# apple_all_pt3.net
KiCad netlist of a schematic drawn in EAGLE
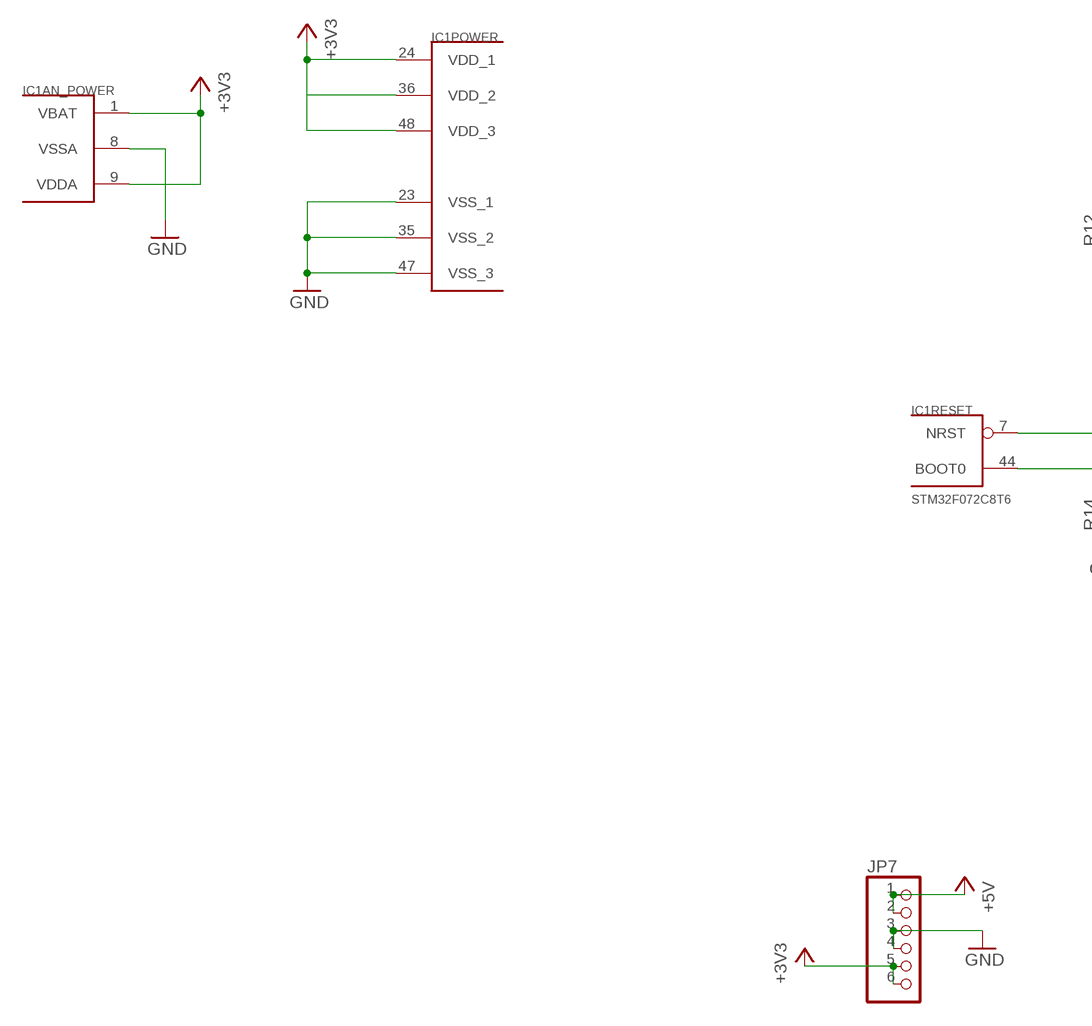
[diagram p0: schematic, sheet 1, part 1 of 2]
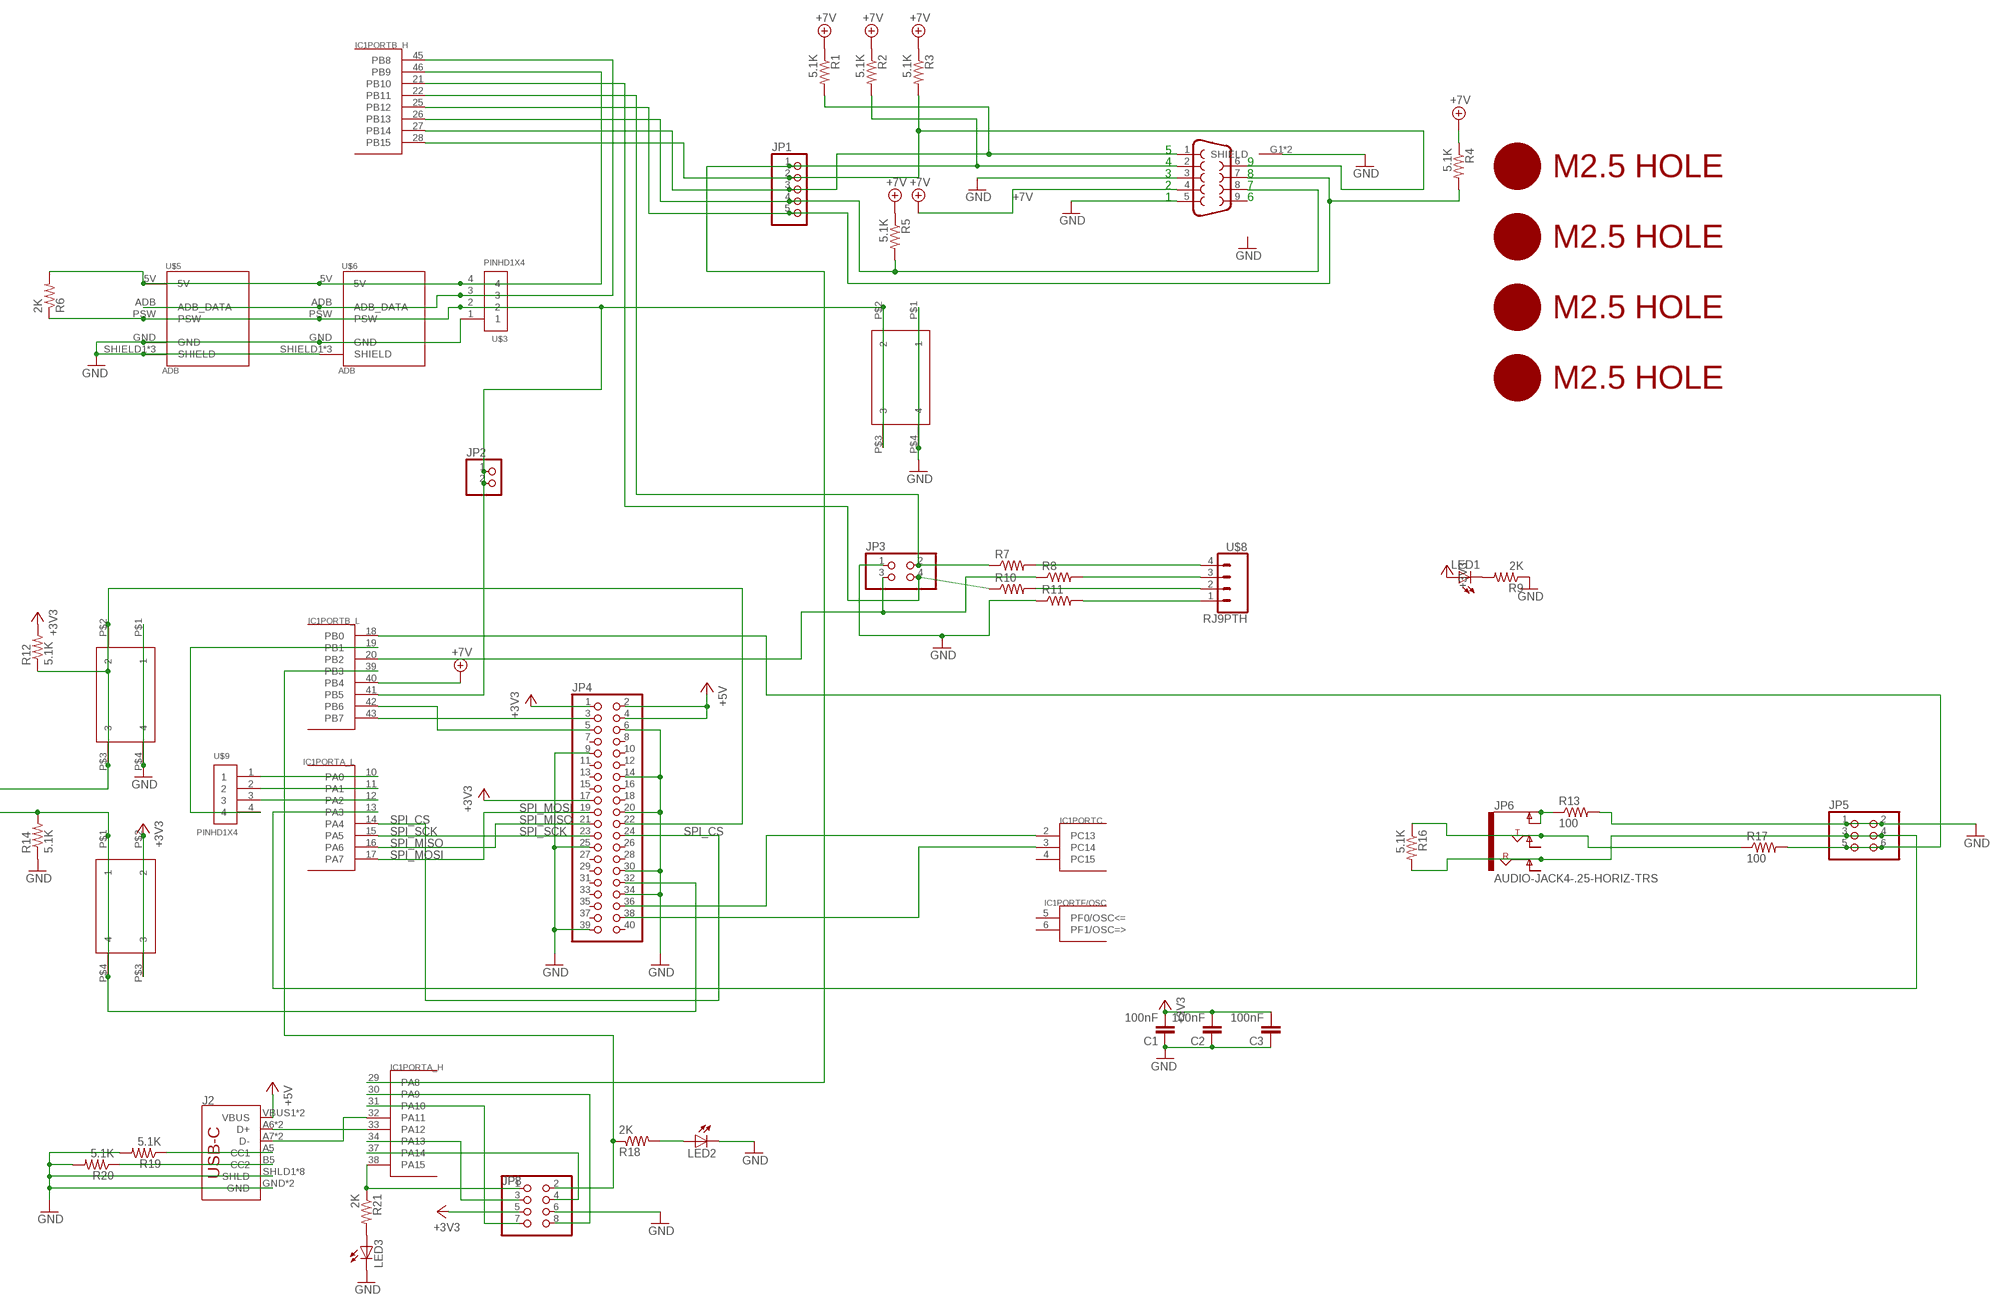
[diagram p1: schematic, sheet 1, part 2 of 2]

(export (version "E")
  (design (tool "Eeschema 10.0.6"))
  (components
    (comp (ref "C1")
      (value "100nF")
      (footprint "eagle-import:0805@1")
      (libsource (lib "eagle-import") (part "CAP0805"))
    )
    (comp (ref "C2")
      (value "100nF")
      (footprint "eagle-import:0805@1")
      (libsource (lib "eagle-import") (part "CAP0805"))
    )
    (comp (ref "C3")
      (value "100nF")
      (footprint "eagle-import:0805@1")
      (libsource (lib "eagle-import") (part "CAP0805"))
    )
    (comp (ref "IC1")
      (value "STM32F072C8T6")
      (footprint "eagle-import:TQFP48")
      (libsource (lib "eagle-import") (part "STM32F072C8T6"))
    )
    (comp (ref "J1")
      (value "DB9FEMALE")
      (footprint "eagle-import:DB9")
      (libsource (lib "eagle-import") (part "DB9FEMALE"))
    )
    (comp (ref "J2")
      (value "USB_C16PIN")
      (footprint "eagle-import:USB-C-16P")
      (libsource (lib "eagle-import") (part "USB_C16PIN"))
    )
    (comp (ref "JP1")
      (value "PINHD-1X5")
      (footprint "eagle-import:1X05")
      (libsource (lib "eagle-import") (part "PINHD-1X5"))
    )
    (comp (ref "JP2")
      (value "PINHD-1X2")
      (footprint "eagle-import:1X02")
      (libsource (lib "eagle-import") (part "PINHD-1X2"))
    )
    (comp (ref "JP3")
      (value "PINHD-2X2")
      (footprint "eagle-import:2X02")
      (libsource (lib "eagle-import") (part "PINHD-2X2"))
    )
    (comp (ref "JP4")
      (value "PINHD-2X20-BIG")
      (footprint "eagle-import:2X20-BIG")
      (libsource (lib "eagle-import") (part "PINHD-2X20-BIG"))
    )
    (comp (ref "JP5")
      (value "PINHD-2X3")
      (footprint "eagle-import:2X03")
      (libsource (lib "eagle-import") (part "PINHD-2X3"))
    )
    (comp (ref "JP6")
      (value "AUDIO-JACK4-.25-HORIZ-TRS")
      (footprint "eagle-import:AUDIO-JACK-.25-INCH-HORIZ-PTH")
      (libsource (lib "eagle-import") (part "AUDIO-JACK4-.25-HORIZ-TRS"))
    )
    (comp (ref "JP7")
      (value "PINHD-1X6CB")
      (footprint "eagle-import:1X06-CLEANBIG")
      (libsource (lib "eagle-import") (part "PINHD-1X6CB"))
    )
    (comp (ref "JP8")
      (value "PINHD-2X4")
      (footprint "eagle-import:2X04")
      (libsource (lib "eagle-import") (part "PINHD-2X4"))
    )
    (comp (ref "LED1")
      (value "LEDCHIP-LED0805")
      (footprint "eagle-import:CHIP-LED0805")
      (libsource (lib "eagle-import") (part "LEDCHIP-LED0805"))
    )
    (comp (ref "LED2")
      (value "LEDCHIP-LED0805")
      (footprint "eagle-import:CHIP-LED0805")
      (libsource (lib "eagle-import") (part "LEDCHIP-LED0805"))
    )
    (comp (ref "LED3")
      (value "LEDCHIP-LED0805")
      (footprint "eagle-import:CHIP-LED0805")
      (libsource (lib "eagle-import") (part "LEDCHIP-LED0805"))
    )
    (comp (ref "R1")
      (value "5.1K")
      (footprint "eagle-import:0805")
      (libsource (lib "eagle-import") (part "RESISTOR0805-RES"))
    )
    (comp (ref "R2")
      (value "5.1K")
      (footprint "eagle-import:0805")
      (libsource (lib "eagle-import") (part "RESISTOR0805-RES"))
    )
    (comp (ref "R3")
      (value "5.1K")
      (footprint "eagle-import:0805")
      (libsource (lib "eagle-import") (part "RESISTOR0805-RES"))
    )
    (comp (ref "R4")
      (value "5.1K")
      (footprint "eagle-import:0805")
      (libsource (lib "eagle-import") (part "RESISTOR0805-RES"))
    )
    (comp (ref "R5")
      (value "5.1K")
      (footprint "eagle-import:0805")
      (libsource (lib "eagle-import") (part "RESISTOR0805-RES"))
    )
    (comp (ref "R6")
      (value "2K")
      (footprint "eagle-import:0805")
      (libsource (lib "eagle-import") (part "RESISTOR0805-RES"))
    )
    (comp (ref "R7")
      (value "200")
      (footprint "eagle-import:0805")
      (libsource (lib "eagle-import") (part "RESISTOR0805-RES"))
    )
    (comp (ref "R8")
      (value "200")
      (footprint "eagle-import:0805")
      (libsource (lib "eagle-import") (part "RESISTOR0805-RES"))
    )
    (comp (ref "R9")
      (value "2K")
      (footprint "eagle-import:0805")
      (libsource (lib "eagle-import") (part "RESISTOR0805-RES"))
    )
    (comp (ref "R10")
      (value "200")
      (footprint "eagle-import:0805")
      (libsource (lib "eagle-import") (part "RESISTOR0805-RES"))
    )
    (comp (ref "R11")
      (value "200")
      (footprint "eagle-import:0805")
      (libsource (lib "eagle-import") (part "RESISTOR0805-RES"))
    )
    (comp (ref "R12")
      (value "5.1K")
      (footprint "eagle-import:0805")
      (libsource (lib "eagle-import") (part "RESISTOR0805-RES"))
    )
    (comp (ref "R13")
      (value "100")
      (footprint "eagle-import:0805")
      (libsource (lib "eagle-import") (part "RESISTOR0805-RES"))
    )
    (comp (ref "R14")
      (value "5.1K")
      (footprint "eagle-import:0805")
      (libsource (lib "eagle-import") (part "RESISTOR0805-RES"))
    )
    (comp (ref "R16")
      (value "5.1K")
      (footprint "eagle-import:0805")
      (libsource (lib "eagle-import") (part "RESISTOR0805-RES"))
    )
    (comp (ref "R17")
      (value "100")
      (footprint "eagle-import:0805")
      (libsource (lib "eagle-import") (part "RESISTOR0805-RES"))
    )
    (comp (ref "R18")
      (value "2K")
      (footprint "eagle-import:0805")
      (libsource (lib "eagle-import") (part "RESISTOR0805-RES"))
    )
    (comp (ref "R19")
      (value "5.1K")
      (footprint "eagle-import:0805")
      (libsource (lib "eagle-import") (part "RESISTOR0805-RES"))
    )
    (comp (ref "R20")
      (value "5.1K")
      (footprint "eagle-import:0805")
      (libsource (lib "eagle-import") (part "RESISTOR0805-RES"))
    )
    (comp (ref "R21")
      (value "2K")
      (footprint "eagle-import:0805")
      (libsource (lib "eagle-import") (part "RESISTOR0805-RES"))
    )
    (comp (ref "SW1")
      (value "324_SW")
      (footprint "eagle-import:342_SWICH_FOOT")
      (libsource (lib "eagle-import") (part "324_SW"))
    )
    (comp (ref "SW2")
      (value "324_SW")
      (footprint "eagle-import:342_SWICH_FOOT")
      (libsource (lib "eagle-import") (part "324_SW"))
    )
    (comp (ref "SW3")
      (value "324_SW")
      (footprint "eagle-import:342_SWICH_FOOT")
      (libsource (lib "eagle-import") (part "324_SW"))
    )
    (comp (ref "U$1")
      (value "M2.5HOLE")
      (footprint "eagle-import:M2.5HOLE")
      (libsource (lib "eagle-import") (part "M2.5HOLE"))
    )
    (comp (ref "U$2")
      (value "M2.5HOLE")
      (footprint "eagle-import:M2.5HOLE")
      (libsource (lib "eagle-import") (part "M2.5HOLE"))
    )
    (comp (ref "U$3")
      (value "PINHD1X4")
      (footprint "eagle-import:1X04-CLEANBIG")
      (libsource (lib "eagle-import") (part "PINHD1X4"))
    )
    (comp (ref "U$4")
      (value "M2.5HOLE")
      (footprint "eagle-import:M2.5HOLE")
      (libsource (lib "eagle-import") (part "M2.5HOLE"))
    )
    (comp (ref "U$5")
      (value "ADB")
      (footprint "eagle-import:DIN4")
      (libsource (lib "eagle-import") (part "ADB"))
    )
    (comp (ref "U$6")
      (value "ADB")
      (footprint "eagle-import:DIN4")
      (libsource (lib "eagle-import") (part "ADB"))
    )
    (comp (ref "U$7")
      (value "M2.5HOLE")
      (footprint "eagle-import:M2.5HOLE")
      (libsource (lib "eagle-import") (part "M2.5HOLE"))
    )
    (comp (ref "U$8")
      (value "RJ9PTH")
      (footprint "eagle-import:RJ9")
      (libsource (lib "eagle-import") (part "RJ9PTH"))
    )
    (comp (ref "U$9")
      (value "PINHD1X4")
      (footprint "eagle-import:1X04-CLEANBIG")
      (libsource (lib "eagle-import") (part "PINHD1X4"))
    )
  )
  (nets
    (net (code "1") (name "+3V3") (class "Default")
      (node (ref "C1") (pin "2") (pinfunction "2_2") (pintype "passive"))
      (node (ref "C2") (pin "2") (pinfunction "2_2") (pintype "passive"))
      (node (ref "C3") (pin "2") (pinfunction "2_2") (pintype "passive"))
      (node (ref "IC1") (pin "1") (pinfunction "VBAT_1") (pintype "power_in"))
      (node (ref "IC1") (pin "24") (pinfunction "VDD_1_24") (pintype "power_in"))
      (node (ref "IC1") (pin "36") (pinfunction "VDD_2_36") (pintype "power_in"))
      (node (ref "IC1") (pin "48") (pinfunction "VDD_3_48") (pintype "power_in"))
      (node (ref "IC1") (pin "9") (pinfunction "VDDA_9") (pintype "power_in"))
      (node (ref "JP4") (pin "1") (pinfunction "1_1") (pintype "passive"))
      (node (ref "JP4") (pin "17") (pinfunction "17_17") (pintype "passive"))
      (node (ref "JP7") (pin "5") (pinfunction "5_5") (pintype "passive"))
      (node (ref "JP7") (pin "6") (pinfunction "6_6") (pintype "passive"))
      (node (ref "JP8") (pin "5") (pinfunction "5_5") (pintype "passive"))
      (node (ref "LED1") (pin "A") (pinfunction "A_A") (pintype "passive"))
      (node (ref "R12") (pin "2") (pinfunction "2_2") (pintype "passive"))
      (node (ref "SW3") (pin "P$2") (pinfunction "2_P$2") (pintype "bidirectional"))
      (node (ref "SW3") (pin "P$3") (pinfunction "3_P$3") (pintype "bidirectional"))
    )
    (net (code "2") (name "+5V") (class "Default")
      (node (ref "J2") (pin "VBUS1") (pinfunction "VBUS_VBUS1") (pintype "bidirectional"))
      (node (ref "J2") (pin "VBUS2") (pinfunction "VBUS_VBUS2") (pintype "bidirectional"))
      (node (ref "JP4") (pin "2") (pinfunction "2_2") (pintype "passive"))
      (node (ref "JP4") (pin "4") (pinfunction "4_4") (pintype "passive"))
      (node (ref "JP7") (pin "1") (pinfunction "1_1") (pintype "passive"))
      (node (ref "JP7") (pin "2") (pinfunction "2_2") (pintype "passive"))
    )
    (net (code "3") (name "+7V") (class "Default")
      (node (ref "IC1") (pin "40") (pinfunction "PB4_40") (pintype "bidirectional"))
      (node (ref "J1") (pin "4") (pinfunction "4_4") (pintype "passive"))
      (node (ref "R1") (pin "1") (pinfunction "1_1") (pintype "passive"))
      (node (ref "R2") (pin "1") (pinfunction "1_1") (pintype "passive"))
      (node (ref "R3") (pin "1") (pinfunction "1_1") (pintype "passive"))
      (node (ref "R4") (pin "1") (pinfunction "1_1") (pintype "passive"))
      (node (ref "R5") (pin "1") (pinfunction "1_1") (pintype "passive"))
    )
    (net (code "4") (name "/SPI_CS") (class "Default")
      (node (ref "IC1") (pin "14") (pinfunction "PA4_14") (pintype "bidirectional"))
      (node (ref "JP4") (pin "24") (pinfunction "24_24") (pintype "passive"))
    )
    (net (code "5") (name "/SPI_MISO") (class "Default")
      (node (ref "IC1") (pin "16") (pinfunction "PA6_16") (pintype "bidirectional"))
      (node (ref "JP4") (pin "21") (pinfunction "21_21") (pintype "passive"))
    )
    (net (code "6") (name "/SPI_MOSI") (class "Default")
      (node (ref "IC1") (pin "17") (pinfunction "PA7_17") (pintype "bidirectional"))
      (node (ref "JP4") (pin "19") (pinfunction "19_19") (pintype "passive"))
    )
    (net (code "7") (name "/SPI_SCK") (class "Default")
      (node (ref "IC1") (pin "15") (pinfunction "PA5_15") (pintype "bidirectional"))
      (node (ref "JP4") (pin "23") (pinfunction "23_23") (pintype "passive"))
    )
    (net (code "8") (name "GND") (class "Default")
      (node (ref "C1") (pin "1") (pinfunction "1_1") (pintype "passive"))
      (node (ref "C2") (pin "1") (pinfunction "1_1") (pintype "passive"))
      (node (ref "C3") (pin "1") (pinfunction "1_1") (pintype "passive"))
      (node (ref "IC1") (pin "23") (pinfunction "VSS_1_23") (pintype "power_in"))
      (node (ref "IC1") (pin "35") (pinfunction "VSS_2_35") (pintype "power_in"))
      (node (ref "IC1") (pin "47") (pinfunction "VSS_3_47") (pintype "power_in"))
      (node (ref "IC1") (pin "8") (pinfunction "VSSA_8") (pintype "power_in"))
      (node (ref "J1") (pin "3") (pinfunction "3_3") (pintype "passive"))
      (node (ref "J1") (pin "5") (pinfunction "5_5") (pintype "passive"))
      (node (ref "J1") (pin "G1") (pinfunction "SHIELD_G1") (pintype "bidirectional"))
      (node (ref "J1") (pin "G2") (pinfunction "SHIELD_G2") (pintype "bidirectional"))
      (node (ref "J2") (pin "GND") (pinfunction "GND_GND") (pintype "bidirectional"))
      (node (ref "J2") (pin "GND2") (pinfunction "GND_GND2") (pintype "bidirectional"))
      (node (ref "J2") (pin "SHLD1") (pinfunction "SHLD_SHLD1") (pintype "bidirectional"))
      (node (ref "J2") (pin "SHLD2") (pinfunction "SHLD_SHLD2") (pintype "bidirectional"))
      (node (ref "J2") (pin "SHLD3") (pinfunction "SHLD_SHLD3") (pintype "bidirectional"))
      (node (ref "J2") (pin "SHLD4") (pinfunction "SHLD_SHLD4") (pintype "bidirectional"))
      (node (ref "J2") (pin "SHLD5") (pinfunction "SHLD_SHLD5") (pintype "bidirectional"))
      (node (ref "J2") (pin "SHLD6") (pinfunction "SHLD_SHLD6") (pintype "bidirectional"))
      (node (ref "J2") (pin "SHLD7") (pinfunction "SHLD_SHLD7") (pintype "bidirectional"))
      (node (ref "J2") (pin "SHLD8") (pinfunction "SHLD_SHLD8") (pintype "bidirectional"))
      (node (ref "JP3") (pin "1") (pinfunction "1_1") (pintype "passive"))
      (node (ref "JP4") (pin "14") (pinfunction "14_14") (pintype "passive"))
      (node (ref "JP4") (pin "20") (pinfunction "20_20") (pintype "passive"))
      (node (ref "JP4") (pin "25") (pinfunction "25_25") (pintype "passive"))
      (node (ref "JP4") (pin "30") (pinfunction "30_30") (pintype "passive"))
      (node (ref "JP4") (pin "34") (pinfunction "34_34") (pintype "passive"))
      (node (ref "JP4") (pin "39") (pinfunction "39_39") (pintype "passive"))
      (node (ref "JP4") (pin "6") (pinfunction "6_6") (pintype "passive"))
      (node (ref "JP4") (pin "9") (pinfunction "9_9") (pintype "passive"))
      (node (ref "JP5") (pin "1") (pinfunction "1_1") (pintype "passive"))
      (node (ref "JP5") (pin "2") (pinfunction "2_2") (pintype "passive"))
      (node (ref "JP7") (pin "3") (pinfunction "3_3") (pintype "passive"))
      (node (ref "JP7") (pin "4") (pinfunction "4_4") (pintype "passive"))
      (node (ref "JP8") (pin "6") (pinfunction "6_6") (pintype "passive"))
      (node (ref "LED2") (pin "C") (pinfunction "C_C") (pintype "passive"))
      (node (ref "LED3") (pin "C") (pinfunction "C_C") (pintype "passive"))
      (node (ref "R11") (pin "1") (pinfunction "1_1") (pintype "passive"))
      (node (ref "R13") (pin "2") (pinfunction "2_2") (pintype "passive"))
      (node (ref "R14") (pin "1") (pinfunction "1_1") (pintype "passive"))
      (node (ref "R19") (pin "2") (pinfunction "2_2") (pintype "passive"))
      (node (ref "R20") (pin "2") (pinfunction "2_2") (pintype "passive"))
      (node (ref "R9") (pin "1") (pinfunction "1_1") (pintype "passive"))
      (node (ref "SW1") (pin "P$1") (pinfunction "1_P$1") (pintype "bidirectional"))
      (node (ref "SW1") (pin "P$4") (pinfunction "4_P$4") (pintype "bidirectional"))
      (node (ref "SW2") (pin "P$1") (pinfunction "1_P$1") (pintype "bidirectional"))
      (node (ref "SW2") (pin "P$4") (pinfunction "4_P$4") (pintype "bidirectional"))
      (node (ref "U$3") (pin "1") (pinfunction "1_1") (pintype "bidirectional"))
      (node (ref "U$5") (pin "GND") (pinfunction "GND_GND") (pintype "bidirectional"))
      (node (ref "U$5") (pin "SHIELD1") (pinfunction "SHIELD_SHIELD1") (pintype "bidirectional"))
      (node (ref "U$5") (pin "SHIELD2") (pinfunction "SHIELD_SHIELD2") (pintype "bidirectional"))
      (node (ref "U$5") (pin "SHIELD3") (pinfunction "SHIELD_SHIELD3") (pintype "bidirectional"))
      (node (ref "U$6") (pin "GND") (pinfunction "GND_GND") (pintype "bidirectional"))
      (node (ref "U$6") (pin "SHIELD1") (pinfunction "SHIELD_SHIELD1") (pintype "bidirectional"))
      (node (ref "U$6") (pin "SHIELD2") (pinfunction "SHIELD_SHIELD2") (pintype "bidirectional"))
      (node (ref "U$6") (pin "SHIELD3") (pinfunction "SHIELD_SHIELD3") (pintype "bidirectional"))
    )
    (net (code "9") (name "Net-(IC1B-PA8)") (class "Default")
      (node (ref "IC1") (pin "29") (pinfunction "PA8_29") (pintype "bidirectional"))
      (node (ref "J1") (pin "2") (pinfunction "2_2") (pintype "passive"))
      (node (ref "JP1") (pin "1") (pinfunction "1_1") (pintype "passive"))
      (node (ref "R2") (pin "2") (pinfunction "2_2") (pintype "passive"))
    )
    (net (code "10") (name "Net-(IC1B-PA9)") (class "Default")
      (node (ref "IC1") (pin "30") (pinfunction "PA9_30") (pintype "bidirectional"))
      (node (ref "JP8") (pin "8") (pinfunction "8_8") (pintype "passive"))
    )
    (net (code "11") (name "Net-(IC1B-PA10)") (class "Default")
      (node (ref "IC1") (pin "31") (pinfunction "PA10_31") (pintype "bidirectional"))
      (node (ref "JP8") (pin "7") (pinfunction "7_7") (pintype "passive"))
    )
    (net (code "12") (name "Net-(IC1B-PA11)") (class "Default")
      (node (ref "IC1") (pin "32") (pinfunction "PA11_32") (pintype "bidirectional"))
      (node (ref "J2") (pin "A7") (pinfunction "D-_A7") (pintype "bidirectional"))
      (node (ref "J2") (pin "B7") (pinfunction "D-_B7") (pintype "bidirectional"))
    )
    (net (code "13") (name "Net-(IC1B-PA12)") (class "Default")
      (node (ref "IC1") (pin "33") (pinfunction "PA12_33") (pintype "bidirectional"))
      (node (ref "J2") (pin "A6") (pinfunction "D+_A6") (pintype "bidirectional"))
      (node (ref "J2") (pin "B6") (pinfunction "D+_B6") (pintype "bidirectional"))
    )
    (net (code "14") (name "Net-(IC1B-PA13)") (class "Default")
      (node (ref "IC1") (pin "34") (pinfunction "PA13_34") (pintype "bidirectional"))
      (node (ref "JP8") (pin "3") (pinfunction "3_3") (pintype "passive"))
    )
    (net (code "15") (name "Net-(IC1B-PA14)") (class "Default")
      (node (ref "IC1") (pin "37") (pinfunction "PA14_37") (pintype "bidirectional"))
      (node (ref "JP8") (pin "4") (pinfunction "4_4") (pintype "passive"))
    )
    (net (code "16") (name "Net-(IC1B-PA15)") (class "Default")
      (node (ref "IC1") (pin "38") (pinfunction "PA15_38") (pintype "bidirectional"))
      (node (ref "JP8") (pin "1") (pinfunction "1_1") (pintype "passive"))
      (node (ref "R21") (pin "1") (pinfunction "1_1") (pintype "passive"))
    )
    (net (code "17") (name "Net-(IC1C-PA0)") (class "Default")
      (node (ref "IC1") (pin "10") (pinfunction "PA0_10") (pintype "bidirectional"))
      (node (ref "U$9") (pin "1") (pinfunction "1_1") (pintype "bidirectional"))
    )
    (net (code "18") (name "Net-(IC1C-PA1)") (class "Default")
      (node (ref "IC1") (pin "11") (pinfunction "PA1_11") (pintype "bidirectional"))
      (node (ref "U$9") (pin "2") (pinfunction "2_2") (pintype "bidirectional"))
    )
    (net (code "19") (name "Net-(IC1C-PA2)") (class "Default")
      (node (ref "IC1") (pin "12") (pinfunction "PA2_12") (pintype "bidirectional"))
      (node (ref "U$9") (pin "3") (pinfunction "3_3") (pintype "bidirectional"))
    )
    (net (code "20") (name "Net-(IC1C-PA3)") (class "Default")
      (node (ref "IC1") (pin "13") (pinfunction "PA3_13") (pintype "bidirectional"))
      (node (ref "JP5") (pin "3") (pinfunction "3_3") (pintype "passive"))
      (node (ref "JP5") (pin "4") (pinfunction "4_4") (pintype "passive"))
      (node (ref "JP6") (pin "RING") (pinfunction "RING_RING") (pintype "bidirectional"))
      (node (ref "R16") (pin "2") (pinfunction "2_2") (pintype "passive"))
    )
    (net (code "21") (name "Net-(IC1D-PB8)") (class "Default")
      (node (ref "IC1") (pin "45") (pinfunction "PB8_45") (pintype "bidirectional"))
      (node (ref "U$3") (pin "3") (pinfunction "3_3") (pintype "bidirectional"))
      (node (ref "U$5") (pin "ADB") (pinfunction "ADB_DATA_ADB") (pintype "bidirectional"))
      (node (ref "U$6") (pin "ADB") (pinfunction "ADB_DATA_ADB") (pintype "bidirectional"))
    )
    (net (code "22") (name "Net-(IC1D-PB9)") (class "Default")
      (node (ref "IC1") (pin "46") (pinfunction "PB9_46") (pintype "bidirectional"))
      (node (ref "R6") (pin "2") (pinfunction "2_2") (pintype "passive"))
      (node (ref "U$3") (pin "4") (pinfunction "4_4") (pintype "bidirectional"))
      (node (ref "U$5") (pin "5V") (pinfunction "5V_5V") (pintype "bidirectional"))
      (node (ref "U$6") (pin "5V") (pinfunction "5V_5V") (pintype "bidirectional"))
    )
    (net (code "23") (name "Net-(IC1D-PB10)") (class "Default")
      (node (ref "IC1") (pin "21") (pinfunction "PB10_21") (pintype "bidirectional"))
      (node (ref "JP3") (pin "4") (pinfunction "4_4") (pintype "passive"))
      (node (ref "R10") (pin "1") (pinfunction "1_1") (pintype "passive"))
    )
    (net (code "24") (name "Net-(IC1D-PB11)") (class "Default")
      (node (ref "IC1") (pin "22") (pinfunction "PB11_22") (pintype "bidirectional"))
      (node (ref "JP3") (pin "2") (pinfunction "2_2") (pintype "passive"))
      (node (ref "R7") (pin "1") (pinfunction "1_1") (pintype "passive"))
    )
    (net (code "25") (name "Net-(IC1D-PB12)") (class "Default")
      (node (ref "IC1") (pin "25") (pinfunction "PB12_25") (pintype "bidirectional"))
      (node (ref "J1") (pin "7") (pinfunction "7_7") (pintype "passive"))
      (node (ref "JP1") (pin "5") (pinfunction "5_5") (pintype "passive"))
      (node (ref "R4") (pin "2") (pinfunction "2_2") (pintype "passive"))
    )
    (net (code "26") (name "Net-(IC1D-PB13)") (class "Default")
      (node (ref "IC1") (pin "26") (pinfunction "PB13_26") (pintype "bidirectional"))
      (node (ref "J1") (pin "8") (pinfunction "8_8") (pintype "passive"))
      (node (ref "JP1") (pin "4") (pinfunction "4_4") (pintype "passive"))
      (node (ref "R5") (pin "2") (pinfunction "2_2") (pintype "passive"))
    )
    (net (code "27") (name "Net-(IC1D-PB14)") (class "Default")
      (node (ref "IC1") (pin "27") (pinfunction "PB14_27") (pintype "bidirectional"))
      (node (ref "J1") (pin "1") (pinfunction "1_1") (pintype "passive"))
      (node (ref "JP1") (pin "3") (pinfunction "3_3") (pintype "passive"))
      (node (ref "R1") (pin "2") (pinfunction "2_2") (pintype "passive"))
    )
    (net (code "28") (name "Net-(IC1D-PB15)") (class "Default")
      (node (ref "IC1") (pin "28") (pinfunction "PB15_28") (pintype "bidirectional"))
      (node (ref "J1") (pin "6") (pinfunction "6_6") (pintype "passive"))
      (node (ref "JP1") (pin "2") (pinfunction "2_2") (pintype "passive"))
      (node (ref "R3") (pin "2") (pinfunction "2_2") (pintype "passive"))
    )
    (net (code "29") (name "Net-(IC1E-PB0)") (class "Default")
      (node (ref "IC1") (pin "18") (pinfunction "PB0_18") (pintype "bidirectional"))
      (node (ref "JP5") (pin "5") (pinfunction "5_5") (pintype "passive"))
      (node (ref "JP5") (pin "6") (pinfunction "6_6") (pintype "passive"))
      (node (ref "R17") (pin "2") (pinfunction "2_2") (pintype "passive"))
    )
    (net (code "30") (name "Net-(IC1E-PB1)") (class "Default")
      (node (ref "IC1") (pin "19") (pinfunction "PB1_19") (pintype "bidirectional"))
      (node (ref "U$9") (pin "4") (pinfunction "4_4") (pintype "bidirectional"))
    )
    (net (code "31") (name "Net-(IC1E-PB2)") (class "Default")
      (node (ref "IC1") (pin "20") (pinfunction "PB2_20") (pintype "bidirectional"))
      (node (ref "JP3") (pin "3") (pinfunction "3_3") (pintype "passive"))
      (node (ref "R8") (pin "1") (pinfunction "1_1") (pintype "passive"))
    )
    (net (code "32") (name "Net-(IC1E-PB3)") (class "Default")
      (node (ref "IC1") (pin "39") (pinfunction "PB3_39") (pintype "bidirectional"))
      (node (ref "JP8") (pin "2") (pinfunction "2_2") (pintype "passive"))
      (node (ref "R18") (pin "1") (pinfunction "1_1") (pintype "passive"))
    )
    (net (code "33") (name "Net-(IC1E-PB5)") (class "Default")
      (node (ref "IC1") (pin "41") (pinfunction "PB5_41") (pintype "bidirectional"))
      (node (ref "JP2") (pin "1") (pinfunction "1_1") (pintype "passive"))
      (node (ref "JP2") (pin "2") (pinfunction "2_2") (pintype "passive"))
      (node (ref "R6") (pin "1") (pinfunction "1_1") (pintype "passive"))
      (node (ref "SW1") (pin "P$2") (pinfunction "2_P$2") (pintype "bidirectional"))
      (node (ref "SW1") (pin "P$3") (pinfunction "3_P$3") (pintype "bidirectional"))
      (node (ref "U$3") (pin "2") (pinfunction "2_2") (pintype "bidirectional"))
      (node (ref "U$5") (pin "PSW") (pinfunction "PSW_PSW") (pintype "bidirectional"))
      (node (ref "U$6") (pin "PSW") (pinfunction "PSW_PSW") (pintype "bidirectional"))
    )
    (net (code "34") (name "Net-(IC1E-PB6)") (class "Default")
      (node (ref "IC1") (pin "42") (pinfunction "PB6_42") (pintype "bidirectional"))
      (node (ref "JP4") (pin "5") (pinfunction "5_5") (pintype "passive"))
    )
    (net (code "35") (name "Net-(IC1E-PB7)") (class "Default")
      (node (ref "IC1") (pin "43") (pinfunction "PB7_43") (pintype "bidirectional"))
      (node (ref "JP4") (pin "3") (pinfunction "3_3") (pintype "passive"))
    )
    (net (code "36") (name "Net-(IC1F-PC13)") (class "Default")
      (node (ref "IC1") (pin "2") (pinfunction "PC13_2") (pintype "bidirectional"))
      (node (ref "JP4") (pin "36") (pinfunction "36_36") (pintype "passive"))
    )
    (net (code "37") (name "Net-(IC1F-PC14)") (class "Default")
      (node (ref "IC1") (pin "3") (pinfunction "PC14_3") (pintype "bidirectional"))
      (node (ref "JP4") (pin "38") (pinfunction "38_38") (pintype "passive"))
    )
    (net (code "38") (name "Net-(IC1I-BOOT0)") (class "Default")
      (node (ref "IC1") (pin "44") (pinfunction "BOOT0_44") (pintype "input"))
      (node (ref "JP4") (pin "32") (pinfunction "32_32") (pintype "passive"))
      (node (ref "R14") (pin "2") (pinfunction "2_2") (pintype "passive"))
      (node (ref "SW3") (pin "P$1") (pinfunction "1_P$1") (pintype "bidirectional"))
      (node (ref "SW3") (pin "P$4") (pinfunction "4_P$4") (pintype "bidirectional"))
    )
    (net (code "39") (name "Net-(IC1I-NRST)") (class "Default")
      (node (ref "IC1") (pin "7") (pinfunction "NRST_7") (pintype "input"))
      (node (ref "JP4") (pin "22") (pinfunction "22_22") (pintype "passive"))
      (node (ref "R12") (pin "1") (pinfunction "1_1") (pintype "passive"))
      (node (ref "SW2") (pin "P$2") (pinfunction "2_P$2") (pintype "bidirectional"))
      (node (ref "SW2") (pin "P$3") (pinfunction "3_P$3") (pintype "bidirectional"))
    )
    (net (code "40") (name "Net-(J2-CC1)") (class "Default")
      (node (ref "J2") (pin "A5") (pinfunction "CC1_A5") (pintype "bidirectional"))
      (node (ref "R19") (pin "1") (pinfunction "1_1") (pintype "passive"))
    )
    (net (code "41") (name "Net-(J2-CC2)") (class "Default")
      (node (ref "J2") (pin "B5") (pinfunction "CC2_B5") (pintype "bidirectional"))
      (node (ref "R20") (pin "1") (pinfunction "1_1") (pintype "passive"))
    )
    (net (code "42") (name "Net-(JP6-EARTH)") (class "Default")
      (node (ref "JP6") (pin "SLEEVE") (pinfunction "EARTH_SLEEVE") (pintype "bidirectional"))
      (node (ref "JP6") (pin "SLEEVE-NORM") (pinfunction "EARTH-NORM_SLEEVE-NORM") (pintype "bidirectional"))
      (node (ref "R13") (pin "1") (pinfunction "1_1") (pintype "passive"))
    )
    (net (code "43") (name "Net-(JP6-PadTIP)") (class "Default")
      (node (ref "JP6") (pin "TIP") (pinfunction "TIP_TIP") (pintype "bidirectional"))
      (node (ref "R16") (pin "1") (pinfunction "1_1") (pintype "passive"))
      (node (ref "R17") (pin "1") (pinfunction "1_1") (pintype "passive"))
    )
    (net (code "44") (name "Net-(LED1-PadC)") (class "Default")
      (node (ref "LED1") (pin "C") (pinfunction "C_C") (pintype "passive"))
      (node (ref "R9") (pin "2") (pinfunction "2_2") (pintype "passive"))
    )
    (net (code "45") (name "Net-(LED2-PadA)") (class "Default")
      (node (ref "LED2") (pin "A") (pinfunction "A_A") (pintype "passive"))
      (node (ref "R18") (pin "2") (pinfunction "2_2") (pintype "passive"))
    )
    (net (code "46") (name "Net-(LED3-PadA)") (class "Default")
      (node (ref "LED3") (pin "A") (pinfunction "A_A") (pintype "passive"))
      (node (ref "R21") (pin "2") (pinfunction "2_2") (pintype "passive"))
    )
    (net (code "47") (name "Net-(R7-Pad2)") (class "Default")
      (node (ref "R7") (pin "2") (pinfunction "2_2") (pintype "passive"))
      (node (ref "U$8") (pin "4") (pinfunction "4_4") (pintype "passive"))
    )
    (net (code "48") (name "Net-(R8-Pad2)") (class "Default")
      (node (ref "R8") (pin "2") (pinfunction "2_2") (pintype "passive"))
      (node (ref "U$8") (pin "3") (pinfunction "3_3") (pintype "passive"))
    )
    (net (code "49") (name "Net-(R10-Pad2)") (class "Default")
      (node (ref "R10") (pin "2") (pinfunction "2_2") (pintype "passive"))
      (node (ref "U$8") (pin "2") (pinfunction "2_2") (pintype "passive"))
    )
    (net (code "50") (name "Net-(R11-Pad2)") (class "Default")
      (node (ref "R11") (pin "2") (pinfunction "2_2") (pintype "passive"))
      (node (ref "U$8") (pin "1") (pinfunction "1_1") (pintype "passive"))
    )
    (net (code "51") (name "unconnected-(IC1F-PC15-Pad4)") (class "Default")
      (node (ref "IC1") (pin "4") (pinfunction "PC15_4") (pintype "bidirectional"))
    )
    (net (code "52") (name "unconnected-(IC1G-PF0{slash}OSC<=-Pad5)") (class "Default")
      (node (ref "IC1") (pin "5") (pinfunction "PF0/OSC<=_5") (pintype "bidirectional"))
    )
    (net (code "53") (name "unconnected-(IC1G-PF1{slash}OSC=>-Pad6)") (class "Default")
      (node (ref "IC1") (pin "6") (pinfunction "PF1/OSC=>_6") (pintype "bidirectional"))
    )
    (net (code "54") (name "unconnected-(J1-Pad9)") (class "Default")
      (node (ref "J1") (pin "9") (pinfunction "9_9") (pintype "passive"))
    )
    (net (code "55") (name "unconnected-(JP4-Pad7)") (class "Default")
      (node (ref "JP4") (pin "7") (pinfunction "7_7") (pintype "passive"))
    )
    (net (code "56") (name "unconnected-(JP4-Pad8)") (class "Default")
      (node (ref "JP4") (pin "8") (pinfunction "8_8") (pintype "passive"))
    )
    (net (code "57") (name "unconnected-(JP4-Pad10)") (class "Default")
      (node (ref "JP4") (pin "10") (pinfunction "10_10") (pintype "passive"))
    )
    (net (code "58") (name "unconnected-(JP4-Pad11)") (class "Default")
      (node (ref "JP4") (pin "11") (pinfunction "11_11") (pintype "passive"))
    )
    (net (code "59") (name "unconnected-(JP4-Pad12)") (class "Default")
      (node (ref "JP4") (pin "12") (pinfunction "12_12") (pintype "passive"))
    )
    (net (code "60") (name "unconnected-(JP4-Pad13)") (class "Default")
      (node (ref "JP4") (pin "13") (pinfunction "13_13") (pintype "passive"))
    )
    (net (code "61") (name "unconnected-(JP4-Pad15)") (class "Default")
      (node (ref "JP4") (pin "15") (pinfunction "15_15") (pintype "passive"))
    )
    (net (code "62") (name "unconnected-(JP4-Pad16)") (class "Default")
      (node (ref "JP4") (pin "16") (pinfunction "16_16") (pintype "passive"))
    )
    (net (code "63") (name "unconnected-(JP4-Pad18)") (class "Default")
      (node (ref "JP4") (pin "18") (pinfunction "18_18") (pintype "passive"))
    )
    (net (code "64") (name "unconnected-(JP4-Pad26)") (class "Default")
      (node (ref "JP4") (pin "26") (pinfunction "26_26") (pintype "passive"))
    )
    (net (code "65") (name "unconnected-(JP4-Pad27)") (class "Default")
      (node (ref "JP4") (pin "27") (pinfunction "27_27") (pintype "passive"))
    )
    (net (code "66") (name "unconnected-(JP4-Pad28)") (class "Default")
      (node (ref "JP4") (pin "28") (pinfunction "28_28") (pintype "passive"))
    )
    (net (code "67") (name "unconnected-(JP4-Pad29)") (class "Default")
      (node (ref "JP4") (pin "29") (pinfunction "29_29") (pintype "passive"))
    )
    (net (code "68") (name "unconnected-(JP4-Pad31)") (class "Default")
      (node (ref "JP4") (pin "31") (pinfunction "31_31") (pintype "passive"))
    )
    (net (code "69") (name "unconnected-(JP4-Pad33)") (class "Default")
      (node (ref "JP4") (pin "33") (pinfunction "33_33") (pintype "passive"))
    )
    (net (code "70") (name "unconnected-(JP4-Pad35)") (class "Default")
      (node (ref "JP4") (pin "35") (pinfunction "35_35") (pintype "passive"))
    )
    (net (code "71") (name "unconnected-(JP4-Pad37)") (class "Default")
      (node (ref "JP4") (pin "37") (pinfunction "37_37") (pintype "passive"))
    )
    (net (code "72") (name "unconnected-(JP4-Pad40)") (class "Default")
      (node (ref "JP4") (pin "40") (pinfunction "40_40") (pintype "passive"))
    )
    (net (code "73") (name "unconnected-(JP6-PadRING-NORM)") (class "Default")
      (node (ref "JP6") (pin "RING-NORM") (pinfunction "RING-NORM_RING-NORM") (pintype "bidirectional"))
    )
    (net (code "74") (name "unconnected-(JP6-PadTIP-NORM)") (class "Default")
      (node (ref "JP6") (pin "TIP-NORM") (pinfunction "TIP-NORM_TIP-NORM") (pintype "bidirectional"))
    )
  )
)
